# CTRL_Circuitry.net
KiCad netlist of a schematic drawn in Altium Designer
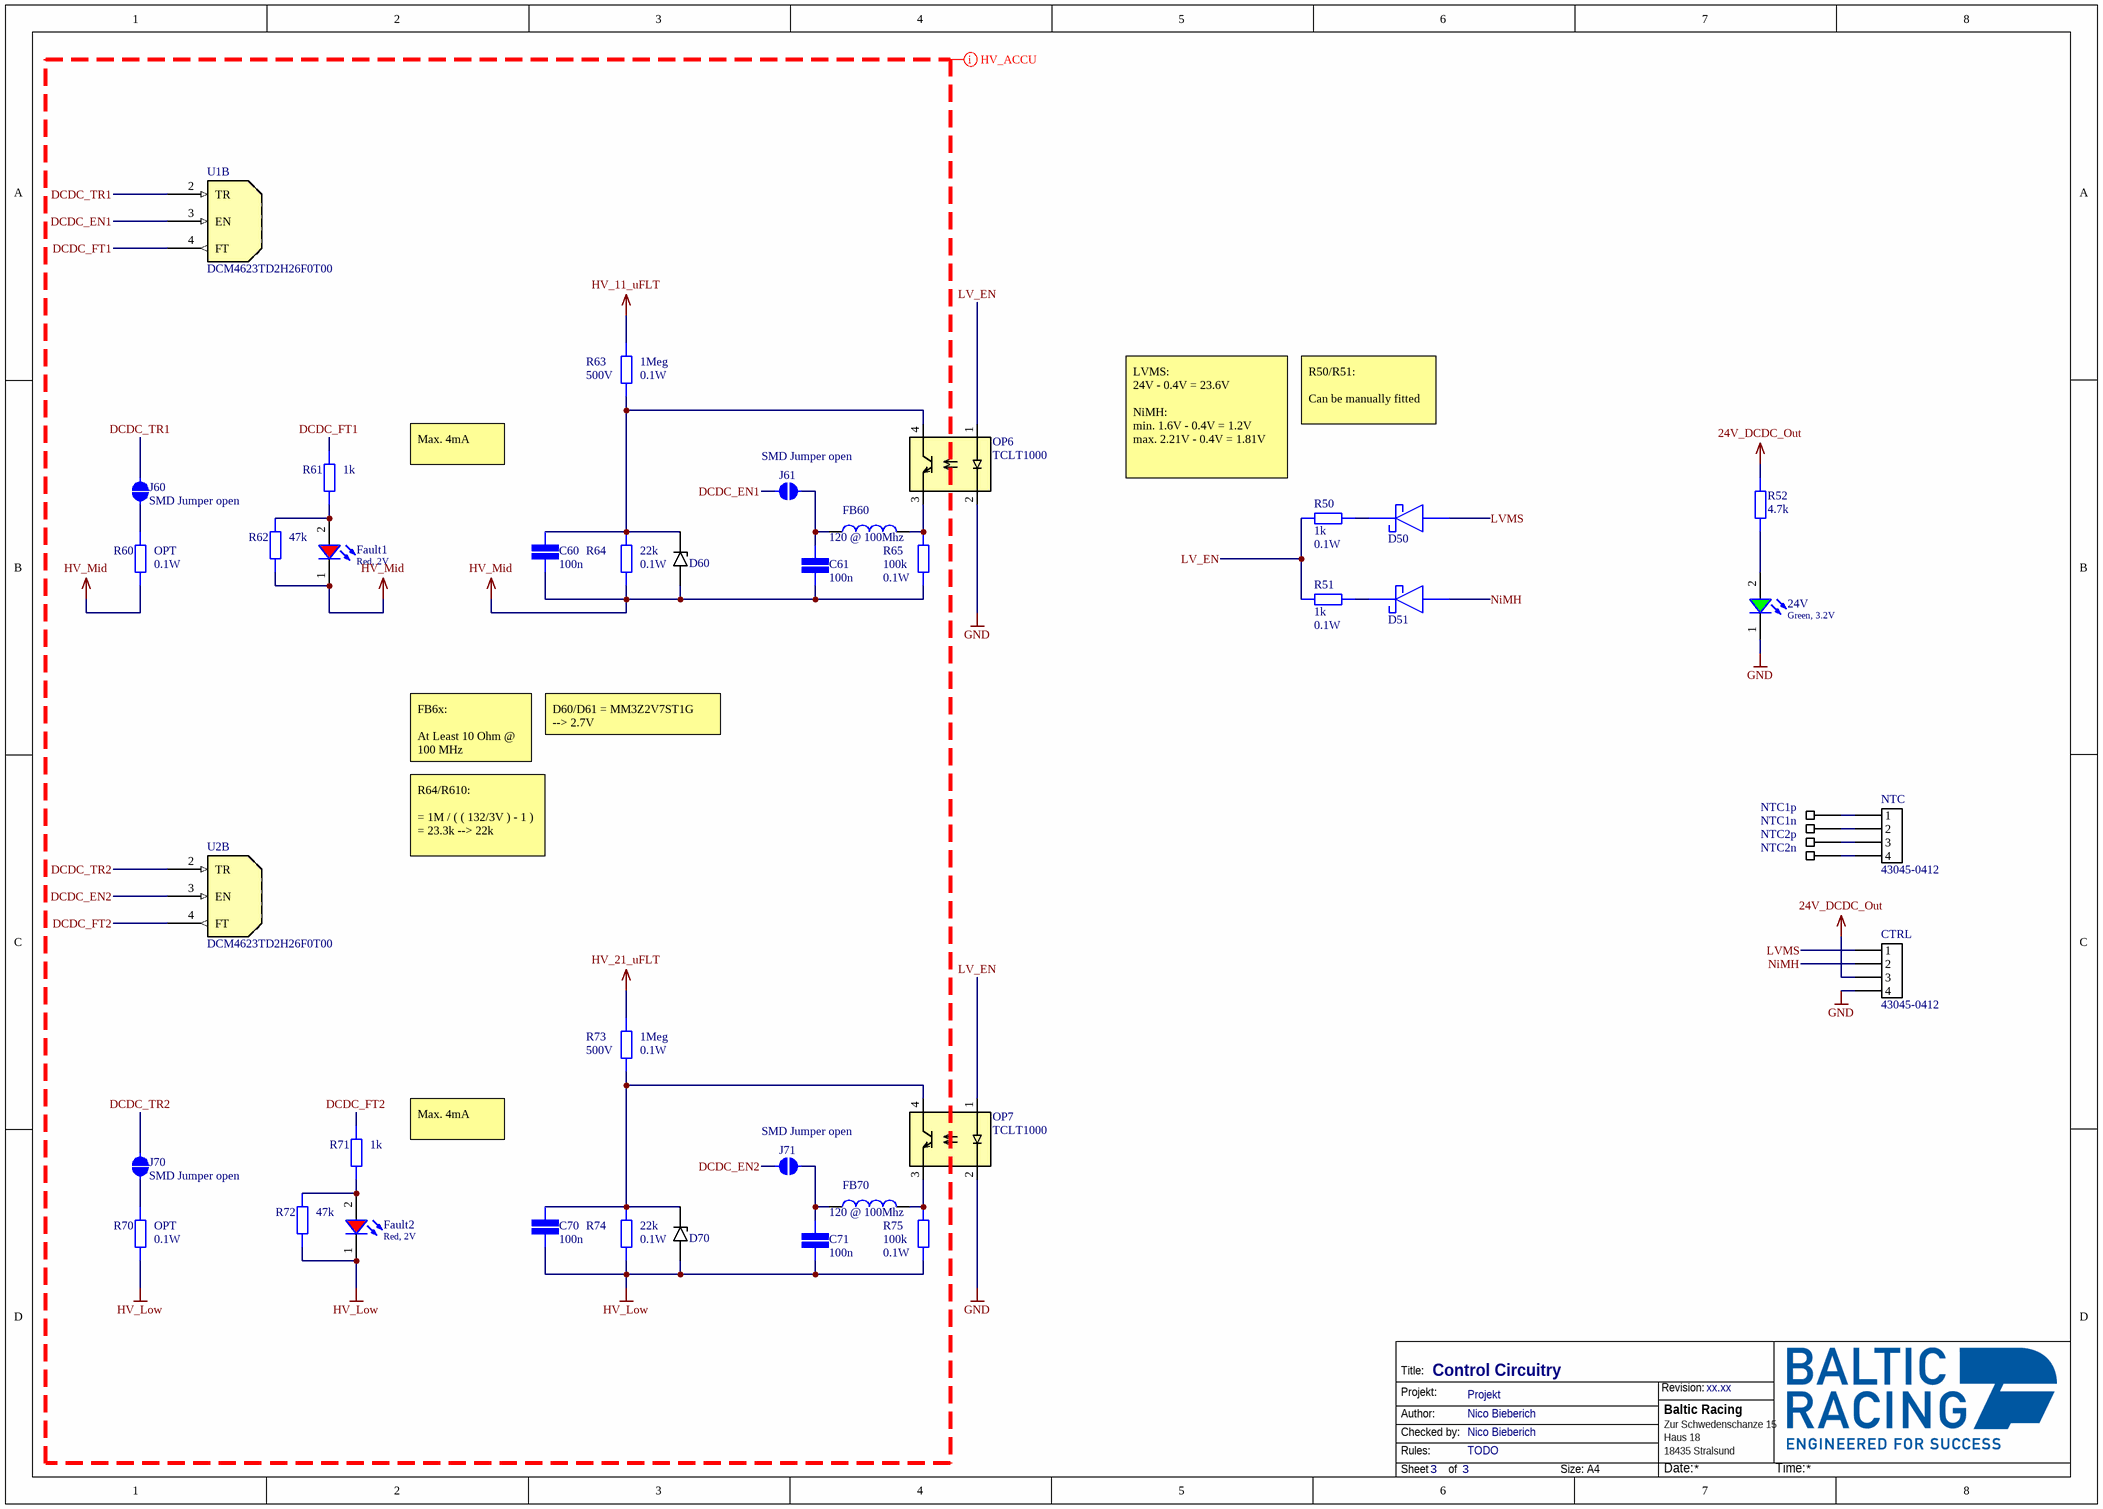
[diagram p0: CTRL_Circuitry.SchDoc]

(export (version "E")
  (design (tool "Eeschema 10.0.6"))
  (components
    (comp (ref "24V")
      (value "Green, 3.2V")
      (footprint "WL-SMCW_0603_H=0.7mm")
      (description "WL-SMCW SMT Mono-color Chip LED Waterclear, size 0603, Green, 3.2V, 140deg")
      (fields (field (name "PART NUMBER") "150060GS75000") (field (name "PUBLISHER") "Wurth Elektronik"))
      (libsource (lib "Altium_WL-SMCW (rev20a)") (part "150060GS75000"))
    )
    (comp (ref "C60")
      (value "100n")
      (footprint "CAP 0603/1608")
      (description "Capacitor with multiple Footprints")
      (fields (field (name "Comment") "SMD Capacitor"))
      (libsource (lib "Standardbauteile") (part "SMD Capacitor"))
    )
    (comp (ref "C61")
      (value "100n")
      (footprint "CAP 0603/1608")
      (description "Capacitor with multiple Footprints")
      (fields (field (name "Comment") "SMD Capacitor"))
      (libsource (lib "Standardbauteile") (part "SMD Capacitor"))
    )
    (comp (ref "C70")
      (value "100n")
      (footprint "CAP 0603/1608")
      (description "Capacitor with multiple Footprints")
      (fields (field (name "Comment") "SMD Capacitor"))
      (libsource (lib "Standardbauteile") (part "SMD Capacitor"))
    )
    (comp (ref "C71")
      (value "100n")
      (footprint "CAP 0603/1608")
      (description "Capacitor with multiple Footprints")
      (fields (field (name "Comment") "SMD Capacitor"))
      (libsource (lib "Standardbauteile") (part "SMD Capacitor"))
    )
    (comp (ref "CTRL")
      (value "43045-0412")
      (footprint "43045-0412")
      (libsource (lib "molex_43045") (part "43045-0412"))
    )
    (comp (ref "D50")
      (value "CUS521,H3F")
      (footprint "SOD-323-2")
      (description "Toshiba CUS521,H3F\r\nShottky-Diode\r\nForward: 390mV, Reverse: 30V")
      (libsource (lib "libNico") (part "CUS521,H3F"))
    )
    (comp (ref "D51")
      (value "CUS521,H3F")
      (footprint "SOD-323-2")
      (description "Toshiba CUS521,H3F\r\nShottky-Diode\r\nForward: 390mV, Reverse: 30V")
      (libsource (lib "libNico") (part "CUS521,H3F"))
    )
    (comp (ref "D60")
      (value "MM3Z2V7ST1G")
      (footprint "SOD-323-2")
      (description "onsemi MM3Z2V7ST1G\r\nZ-Diode, 2,7V")
      (libsource (lib "libNico") (part "MM3Z2V7ST1G"))
    )
    (comp (ref "D70")
      (value "MM3Z2V7ST1G")
      (footprint "SOD-323-2")
      (description "onsemi MM3Z2V7ST1G\r\nZ-Diode, 2,7V")
      (libsource (lib "libNico") (part "MM3Z2V7ST1G"))
    )
    (comp (ref "Fault1")
      (value "Red, 2V")
      (footprint "WL-SMCW_0603_H=0.7mm")
      (description "WL-SMCW SMT Mono-color Chip LED Waterclear, size 0603, Red, 2V, 140deg")
      (fields (field (name "PART NUMBER") "150060RS75000") (field (name "PUBLISHER") "Wurth Elektronik"))
      (libsource (lib "Altium_WL-SMCW (rev20a)") (part "150060RS75000"))
    )
    (comp (ref "Fault2")
      (value "Red, 2V")
      (footprint "WL-SMCW_0603_H=0.7mm")
      (description "WL-SMCW SMT Mono-color Chip LED Waterclear, size 0603, Red, 2V, 140deg")
      (fields (field (name "PART NUMBER") "150060RS75000") (field (name "PUBLISHER") "Wurth Elektronik"))
      (libsource (lib "Altium_WL-SMCW (rev20a)") (part "150060RS75000"))
    )
    (comp (ref "FB60")
      (value "120 @ 100Mhz")
      (footprint "WE-CBA_0603_L1.6W0.8H0.8_HF/HS/WB")
      (description "WE-CBA SMT EMI Suppression Ferrite Bead, size 0603, 120Ohm, 0.5A")
      (fields
        (field (name "MANUFACTURER PART NUMBER") "782631131")
        (field (name "MANUFACTURER") "Wurth Elektronik")
      )
      (libsource (lib "Altium_WE-CBA (rev22d)") (part "782631131"))
    )
    (comp (ref "FB70")
      (value "120 @ 100Mhz")
      (footprint "WE-CBA_0603_L1.6W0.8H0.8_HF/HS/WB")
      (description "WE-CBA SMT EMI Suppression Ferrite Bead, size 0603, 120Ohm, 0.5A")
      (fields
        (field (name "MANUFACTURER PART NUMBER") "782631131")
        (field (name "MANUFACTURER") "Wurth Elektronik")
      )
      (libsource (lib "Altium_WE-CBA (rev22d)") (part "782631131"))
    )
    (comp (ref "J60")
      (value "SMD Jumper open")
      (footprint "SMD-JUMPER-OPEN")
      (libsource (lib "Standardbauteile") (part "SMD Jumper open"))
    )
    (comp (ref "J61")
      (value "SMD Jumper open")
      (footprint "SMD-JUMPER-OPEN")
      (libsource (lib "Standardbauteile") (part "SMD Jumper open"))
    )
    (comp (ref "J70")
      (value "SMD Jumper open")
      (footprint "SMD-JUMPER-OPEN")
      (libsource (lib "Standardbauteile") (part "SMD Jumper open"))
    )
    (comp (ref "J71")
      (value "SMD Jumper open")
      (footprint "SMD-JUMPER-OPEN")
      (libsource (lib "Standardbauteile") (part "SMD Jumper open"))
    )
    (comp (ref "NTC")
      (value "43045-0412")
      (footprint "43045-0412")
      (libsource (lib "molex_43045") (part "43045-0412"))
    )
    (comp (ref "NTC1n")
      (value "Pad")
      (footprint "Generic_Pad_1.5x1.5")
      (description "Pad 1.5mm x 1.5mm")
      (libsource (lib "libNico") (part "Generic_Pad_1.5x1.5"))
    )
    (comp (ref "NTC1p")
      (value "Pad")
      (footprint "Generic_Pad_1.5x1.5")
      (description "Pad 1.5mm x 1.5mm")
      (libsource (lib "libNico") (part "Generic_Pad_1.5x1.5"))
    )
    (comp (ref "NTC2n")
      (value "Pad")
      (footprint "Generic_Pad_1.5x1.5")
      (description "Pad 1.5mm x 1.5mm")
      (libsource (lib "libNico") (part "Generic_Pad_1.5x1.5"))
    )
    (comp (ref "NTC2p")
      (value "Pad")
      (footprint "Generic_Pad_1.5x1.5")
      (description "Pad 1.5mm x 1.5mm")
      (libsource (lib "libNico") (part "Generic_Pad_1.5x1.5"))
    )
    (comp (ref "OP6")
      (value "TCLT1000")
      (footprint "SOP-4L")
      (description "Opto-Isolator\r\nVishay TLCT100 series\r\n600V, 5mA, V_ISO= 5 kV (RMS)")
      (libsource (lib "libNico") (part "TCLT1000"))
    )
    (comp (ref "OP7")
      (value "TCLT1000")
      (footprint "SOP-4L")
      (description "Opto-Isolator\r\nVishay TLCT100 series\r\n600V, 5mA, V_ISO= 5 kV (RMS)")
      (libsource (lib "libNico") (part "TCLT1000"))
    )
    (comp (ref "R50")
      (value "1k")
      (footprint "STACKPOLE CSR0603")
      (description "Resistor with multiple footprints")
      (fields (field (name "POWER") "0.1W") (field (name "Comment") "SMD Resistor"))
      (libsource (lib "Standardbauteile") (part "SMD Resistor"))
    )
    (comp (ref "R51")
      (value "1k")
      (footprint "STACKPOLE CSR0603")
      (description "Resistor with multiple footprints")
      (fields (field (name "POWER") "0.1W") (field (name "Comment") "SMD Resistor"))
      (libsource (lib "Standardbauteile") (part "SMD Resistor"))
    )
    (comp (ref "R52")
      (value "4.7k")
      (footprint "STACKPOLE CSR0603")
      (description "Resistor with multiple footprints")
      (fields (field (name "POWER") "0.1 W") (field (name "Comment") "SMD Resistor"))
      (libsource (lib "Standardbauteile") (part "SMD Resistor"))
    )
    (comp (ref "R60")
      (value "OPT")
      (footprint "STACKPOLE CSR0603")
      (description "Resistor with multiple footprints")
      (fields (field (name "POWER") "0.1W") (field (name "Comment") "SMD Resistor"))
      (libsource (lib "Standardbauteile") (part "SMD Resistor"))
    )
    (comp (ref "R61")
      (value "1k")
      (footprint "STACKPOLE CSR0603")
      (description "Resistor with multiple footprints")
      (fields (field (name "POWER") "0.1W") (field (name "Comment") "SMD Resistor"))
      (libsource (lib "Standardbauteile") (part "SMD Resistor"))
    )
    (comp (ref "R62")
      (value "47k")
      (footprint "STACKPOLE CSR0603")
      (description "Resistor with multiple footprints")
      (fields (field (name "POWER") "0.1W") (field (name "Comment") "SMD Resistor"))
      (libsource (lib "Standardbauteile") (part "SMD Resistor"))
    )
    (comp (ref "R63")
      (value "1Meg")
      (footprint "STACKPOLE CSRN2512")
      (description "Resistor with multiple footprints")
      (fields
        (field (name "VOLTAGE") "500V")
        (field (name "POWER") "0.1W")
        (field (name "Comment") "SMD Resistor")
      )
      (libsource (lib "Standardbauteile") (part "SMD Resistor"))
    )
    (comp (ref "R64")
      (value "22k")
      (footprint "STACKPOLE CSR0603")
      (description "Resistor with multiple footprints")
      (fields (field (name "POWER") "0.1W") (field (name "Comment") "SMD Resistor"))
      (libsource (lib "Standardbauteile") (part "SMD Resistor"))
    )
    (comp (ref "R65")
      (value "100k")
      (footprint "STACKPOLE CSR0603")
      (description "Resistor with multiple footprints")
      (fields (field (name "POWER") "0.1W") (field (name "Comment") "SMD Resistor"))
      (libsource (lib "Standardbauteile") (part "SMD Resistor"))
    )
    (comp (ref "R70")
      (value "OPT")
      (footprint "STACKPOLE CSR0603")
      (description "Resistor with multiple footprints")
      (fields (field (name "POWER") "0.1W") (field (name "Comment") "SMD Resistor"))
      (libsource (lib "Standardbauteile") (part "SMD Resistor"))
    )
    (comp (ref "R71")
      (value "1k")
      (footprint "STACKPOLE CSR0603")
      (description "Resistor with multiple footprints")
      (fields (field (name "POWER") "0.1W") (field (name "Comment") "SMD Resistor"))
      (libsource (lib "Standardbauteile") (part "SMD Resistor"))
    )
    (comp (ref "R72")
      (value "47k")
      (footprint "STACKPOLE CSR0603")
      (description "Resistor with multiple footprints")
      (fields (field (name "POWER") "0.1W") (field (name "Comment") "SMD Resistor"))
      (libsource (lib "Standardbauteile") (part "SMD Resistor"))
    )
    (comp (ref "R73")
      (value "1Meg")
      (footprint "STACKPOLE CSRN2512")
      (description "Resistor with multiple footprints")
      (fields
        (field (name "VOLTAGE") "500V")
        (field (name "POWER") "0.1W")
        (field (name "Comment") "SMD Resistor")
      )
      (libsource (lib "Standardbauteile") (part "SMD Resistor"))
    )
    (comp (ref "R74")
      (value "22k")
      (footprint "STACKPOLE CSR0603")
      (description "Resistor with multiple footprints")
      (fields (field (name "POWER") "0.1W") (field (name "Comment") "SMD Resistor"))
      (libsource (lib "Standardbauteile") (part "SMD Resistor"))
    )
    (comp (ref "R75")
      (value "100k")
      (footprint "STACKPOLE CSR0603")
      (description "Resistor with multiple footprints")
      (fields (field (name "POWER") "0.1W") (field (name "Comment") "SMD Resistor"))
      (libsource (lib "Standardbauteile") (part "SMD Resistor"))
    )
    (comp (ref "U1")
      (value "DCM4623")
      (footprint "DCM4623")
      (description "VICOR DCM® DC-DC Converter Module")
      (fields (field (name "MODEL") "DCM4623TD2H26F0T00"))
      (libsource (lib "libNico") (part "DCM4623"))
    )
    (comp (ref "U2")
      (value "DCM4623")
      (footprint "DCM4623")
      (description "VICOR DCM® DC-DC Converter Module")
      (fields (field (name "MODEL") "DCM4623TD2H26F0T00"))
      (libsource (lib "libNico") (part "DCM4623"))
    )
  )
  (nets
    (net (code "1") (name "/DCDC_EN1") (class "Default")
      (node (ref "J61") (pin "2") (pinfunction "2_2") (pintype "passive"))
      (node (ref "U1") (pin "3") (pinfunction "EN_3") (pintype "input"))
    )
    (net (code "2") (name "/DCDC_EN2") (class "Default")
      (node (ref "J71") (pin "2") (pinfunction "2_2") (pintype "passive"))
      (node (ref "U2") (pin "3") (pinfunction "EN_3") (pintype "input"))
    )
    (net (code "3") (name "/DCDC_FT1") (class "Default")
      (node (ref "R61") (pin "2") (pinfunction "2_2") (pintype "passive"))
      (node (ref "U1") (pin "4") (pinfunction "FT_4") (pintype "output"))
    )
    (net (code "4") (name "/DCDC_FT2") (class "Default")
      (node (ref "R71") (pin "2") (pinfunction "2_2") (pintype "passive"))
      (node (ref "U2") (pin "4") (pinfunction "FT_4") (pintype "output"))
    )
    (net (code "5") (name "/DCDC_TR1") (class "Default")
      (node (ref "J60") (pin "2") (pinfunction "2_2") (pintype "passive"))
      (node (ref "U1") (pin "2") (pinfunction "TR_2") (pintype "input"))
    )
    (net (code "6") (name "/DCDC_TR2") (class "Default")
      (node (ref "J70") (pin "2") (pinfunction "2_2") (pintype "passive"))
      (node (ref "U2") (pin "2") (pinfunction "TR_2") (pintype "input"))
    )
    (net (code "7") (name "/LVMS") (class "Default")
      (node (ref "CTRL") (pin "1") (pinfunction "1_1") (pintype "passive"))
      (node (ref "D50") (pin "2A") (pinfunction "A_2A") (pintype "passive"))
    )
    (net (code "8") (name "/LV_EN") (class "Default")
      (node (ref "OP6") (pin "1") (pinfunction "DA_1") (pintype "passive"))
      (node (ref "OP7") (pin "1") (pinfunction "DA_1") (pintype "passive"))
      (node (ref "R50") (pin "2") (pinfunction "2_2") (pintype "passive"))
      (node (ref "R51") (pin "2") (pinfunction "2_2") (pintype "passive"))
    )
    (net (code "9") (name "/NiMH") (class "Default")
      (node (ref "CTRL") (pin "2") (pinfunction "2_2") (pintype "passive"))
      (node (ref "D51") (pin "2A") (pinfunction "A_2A") (pintype "passive"))
    )
    (net (code "10") (name "24V_DCDC_Out") (class "Default")
      (node (ref "CTRL") (pin "3") (pinfunction "3_3") (pintype "passive"))
      (node (ref "R52") (pin "2") (pinfunction "2_2") (pintype "passive"))
    )
    (net (code "11") (name "GND") (class "Default")
      (node (ref "24V") (pin "1") (pinfunction "K_1") (pintype "passive"))
      (node (ref "CTRL") (pin "4") (pinfunction "4_4") (pintype "passive"))
      (node (ref "OP6") (pin "2") (pinfunction "DC_2") (pintype "passive"))
      (node (ref "OP7") (pin "2") (pinfunction "DC_2") (pintype "passive"))
    )
    (net (code "12") (name "HV_11_uFLT") (class "Default")
      (node (ref "R63") (pin "2") (pinfunction "2_2") (pintype "passive"))
    )
    (net (code "13") (name "HV_21_uFLT") (class "Default")
      (node (ref "R73") (pin "2") (pinfunction "2_2") (pintype "passive"))
    )
    (net (code "14") (name "HV_Low") (class "Default")
      (node (ref "C70") (pin "1") (pinfunction "1_1") (pintype "passive"))
      (node (ref "C71") (pin "1") (pinfunction "1_1") (pintype "passive"))
      (node (ref "D70") (pin "2A") (pinfunction "A_2A") (pintype "passive"))
      (node (ref "Fault2") (pin "1") (pinfunction "K_1") (pintype "passive"))
      (node (ref "R70") (pin "1") (pinfunction "1_1") (pintype "passive"))
      (node (ref "R72") (pin "1") (pinfunction "1_1") (pintype "passive"))
      (node (ref "R74") (pin "1") (pinfunction "1_1") (pintype "passive"))
      (node (ref "R75") (pin "1") (pinfunction "1_1") (pintype "passive"))
    )
    (net (code "15") (name "HV_Mid") (class "Default")
      (node (ref "C60") (pin "1") (pinfunction "1_1") (pintype "passive"))
      (node (ref "C61") (pin "1") (pinfunction "1_1") (pintype "passive"))
      (node (ref "D60") (pin "2A") (pinfunction "A_2A") (pintype "passive"))
      (node (ref "Fault1") (pin "1") (pinfunction "K_1") (pintype "passive"))
      (node (ref "R60") (pin "1") (pinfunction "1_1") (pintype "passive"))
      (node (ref "R62") (pin "1") (pinfunction "1_1") (pintype "passive"))
      (node (ref "R64") (pin "1") (pinfunction "1_1") (pintype "passive"))
      (node (ref "R65") (pin "1") (pinfunction "1_1") (pintype "passive"))
    )
    (net (code "16") (name "Net-(24V-A)") (class "Default")
      (node (ref "24V") (pin "2") (pinfunction "A_2") (pintype "passive"))
      (node (ref "R52") (pin "1") (pinfunction "1_1") (pintype "passive"))
    )
    (net (code "17") (name "Net-(C61-Pad2)") (class "Default")
      (node (ref "C61") (pin "2") (pinfunction "2_2") (pintype "passive"))
      (node (ref "FB60") (pin "1") (pinfunction "1_1") (pintype "passive"))
      (node (ref "J61") (pin "1") (pinfunction "1_1") (pintype "passive"))
    )
    (net (code "18") (name "Net-(C71-Pad2)") (class "Default")
      (node (ref "C71") (pin "2") (pinfunction "2_2") (pintype "passive"))
      (node (ref "FB70") (pin "1") (pinfunction "1_1") (pintype "passive"))
      (node (ref "J71") (pin "1") (pinfunction "1_1") (pintype "passive"))
    )
    (net (code "19") (name "Net-(D50-C)") (class "Default")
      (node (ref "D50") (pin "1C") (pinfunction "C_1C") (pintype "passive"))
      (node (ref "R50") (pin "1") (pinfunction "1_1") (pintype "passive"))
    )
    (net (code "20") (name "Net-(D51-C)") (class "Default")
      (node (ref "D51") (pin "1C") (pinfunction "C_1C") (pintype "passive"))
      (node (ref "R51") (pin "1") (pinfunction "1_1") (pintype "passive"))
    )
    (net (code "21") (name "Net-(D60-C)") (class "Default")
      (node (ref "C60") (pin "2") (pinfunction "2_2") (pintype "passive"))
      (node (ref "D60") (pin "1C") (pinfunction "C_1C") (pintype "passive"))
      (node (ref "OP6") (pin "4") (pinfunction "TC_4") (pintype "passive"))
      (node (ref "R63") (pin "1") (pinfunction "1_1") (pintype "passive"))
      (node (ref "R64") (pin "2") (pinfunction "2_2") (pintype "passive"))
    )
    (net (code "22") (name "Net-(D70-C)") (class "Default")
      (node (ref "C70") (pin "2") (pinfunction "2_2") (pintype "passive"))
      (node (ref "D70") (pin "1C") (pinfunction "C_1C") (pintype "passive"))
      (node (ref "OP7") (pin "4") (pinfunction "TC_4") (pintype "passive"))
      (node (ref "R73") (pin "1") (pinfunction "1_1") (pintype "passive"))
      (node (ref "R74") (pin "2") (pinfunction "2_2") (pintype "passive"))
    )
    (net (code "23") (name "Net-(Fault1-A)") (class "Default")
      (node (ref "Fault1") (pin "2") (pinfunction "A_2") (pintype "passive"))
      (node (ref "R61") (pin "1") (pinfunction "1_1") (pintype "passive"))
      (node (ref "R62") (pin "2") (pinfunction "2_2") (pintype "passive"))
    )
    (net (code "24") (name "Net-(Fault2-A)") (class "Default")
      (node (ref "Fault2") (pin "2") (pinfunction "A_2") (pintype "passive"))
      (node (ref "R71") (pin "1") (pinfunction "1_1") (pintype "passive"))
      (node (ref "R72") (pin "2") (pinfunction "2_2") (pintype "passive"))
    )
    (net (code "25") (name "Net-(J60-Pad1)") (class "Default")
      (node (ref "J60") (pin "1") (pinfunction "1_1") (pintype "passive"))
      (node (ref "R60") (pin "2") (pinfunction "2_2") (pintype "passive"))
    )
    (net (code "26") (name "Net-(J70-Pad1)") (class "Default")
      (node (ref "J70") (pin "1") (pinfunction "1_1") (pintype "passive"))
      (node (ref "R70") (pin "2") (pinfunction "2_2") (pintype "passive"))
    )
    (net (code "27") (name "Net-(NTC-Pad1)") (class "Default")
      (node (ref "NTC") (pin "1") (pinfunction "1_1") (pintype "passive"))
      (node (ref "NTC1p") (pin "P") (pinfunction "Pad_P") (pintype "passive"))
    )
    (net (code "28") (name "Net-(NTC-Pad2)") (class "Default")
      (node (ref "NTC") (pin "2") (pinfunction "2_2") (pintype "passive"))
      (node (ref "NTC1n") (pin "P") (pinfunction "Pad_P") (pintype "passive"))
    )
    (net (code "29") (name "Net-(NTC-Pad3)") (class "Default")
      (node (ref "NTC") (pin "3") (pinfunction "3_3") (pintype "passive"))
      (node (ref "NTC2p") (pin "P") (pinfunction "Pad_P") (pintype "passive"))
    )
    (net (code "30") (name "Net-(NTC-Pad4)") (class "Default")
      (node (ref "NTC") (pin "4") (pinfunction "4_4") (pintype "passive"))
      (node (ref "NTC2n") (pin "P") (pinfunction "Pad_P") (pintype "passive"))
    )
    (net (code "31") (name "Net-(OP6-TE)") (class "Default")
      (node (ref "FB60") (pin "2") (pinfunction "2_2") (pintype "passive"))
      (node (ref "OP6") (pin "3") (pinfunction "TE_3") (pintype "passive"))
      (node (ref "R65") (pin "2") (pinfunction "2_2") (pintype "passive"))
    )
    (net (code "32") (name "Net-(OP7-TE)") (class "Default")
      (node (ref "FB70") (pin "2") (pinfunction "2_2") (pintype "passive"))
      (node (ref "OP7") (pin "3") (pinfunction "TE_3") (pintype "passive"))
      (node (ref "R75") (pin "2") (pinfunction "2_2") (pintype "passive"))
    )
  )
)
